# Droid_meter_rev2.net
KiCad netlist of a schematic drawn in EAGLE
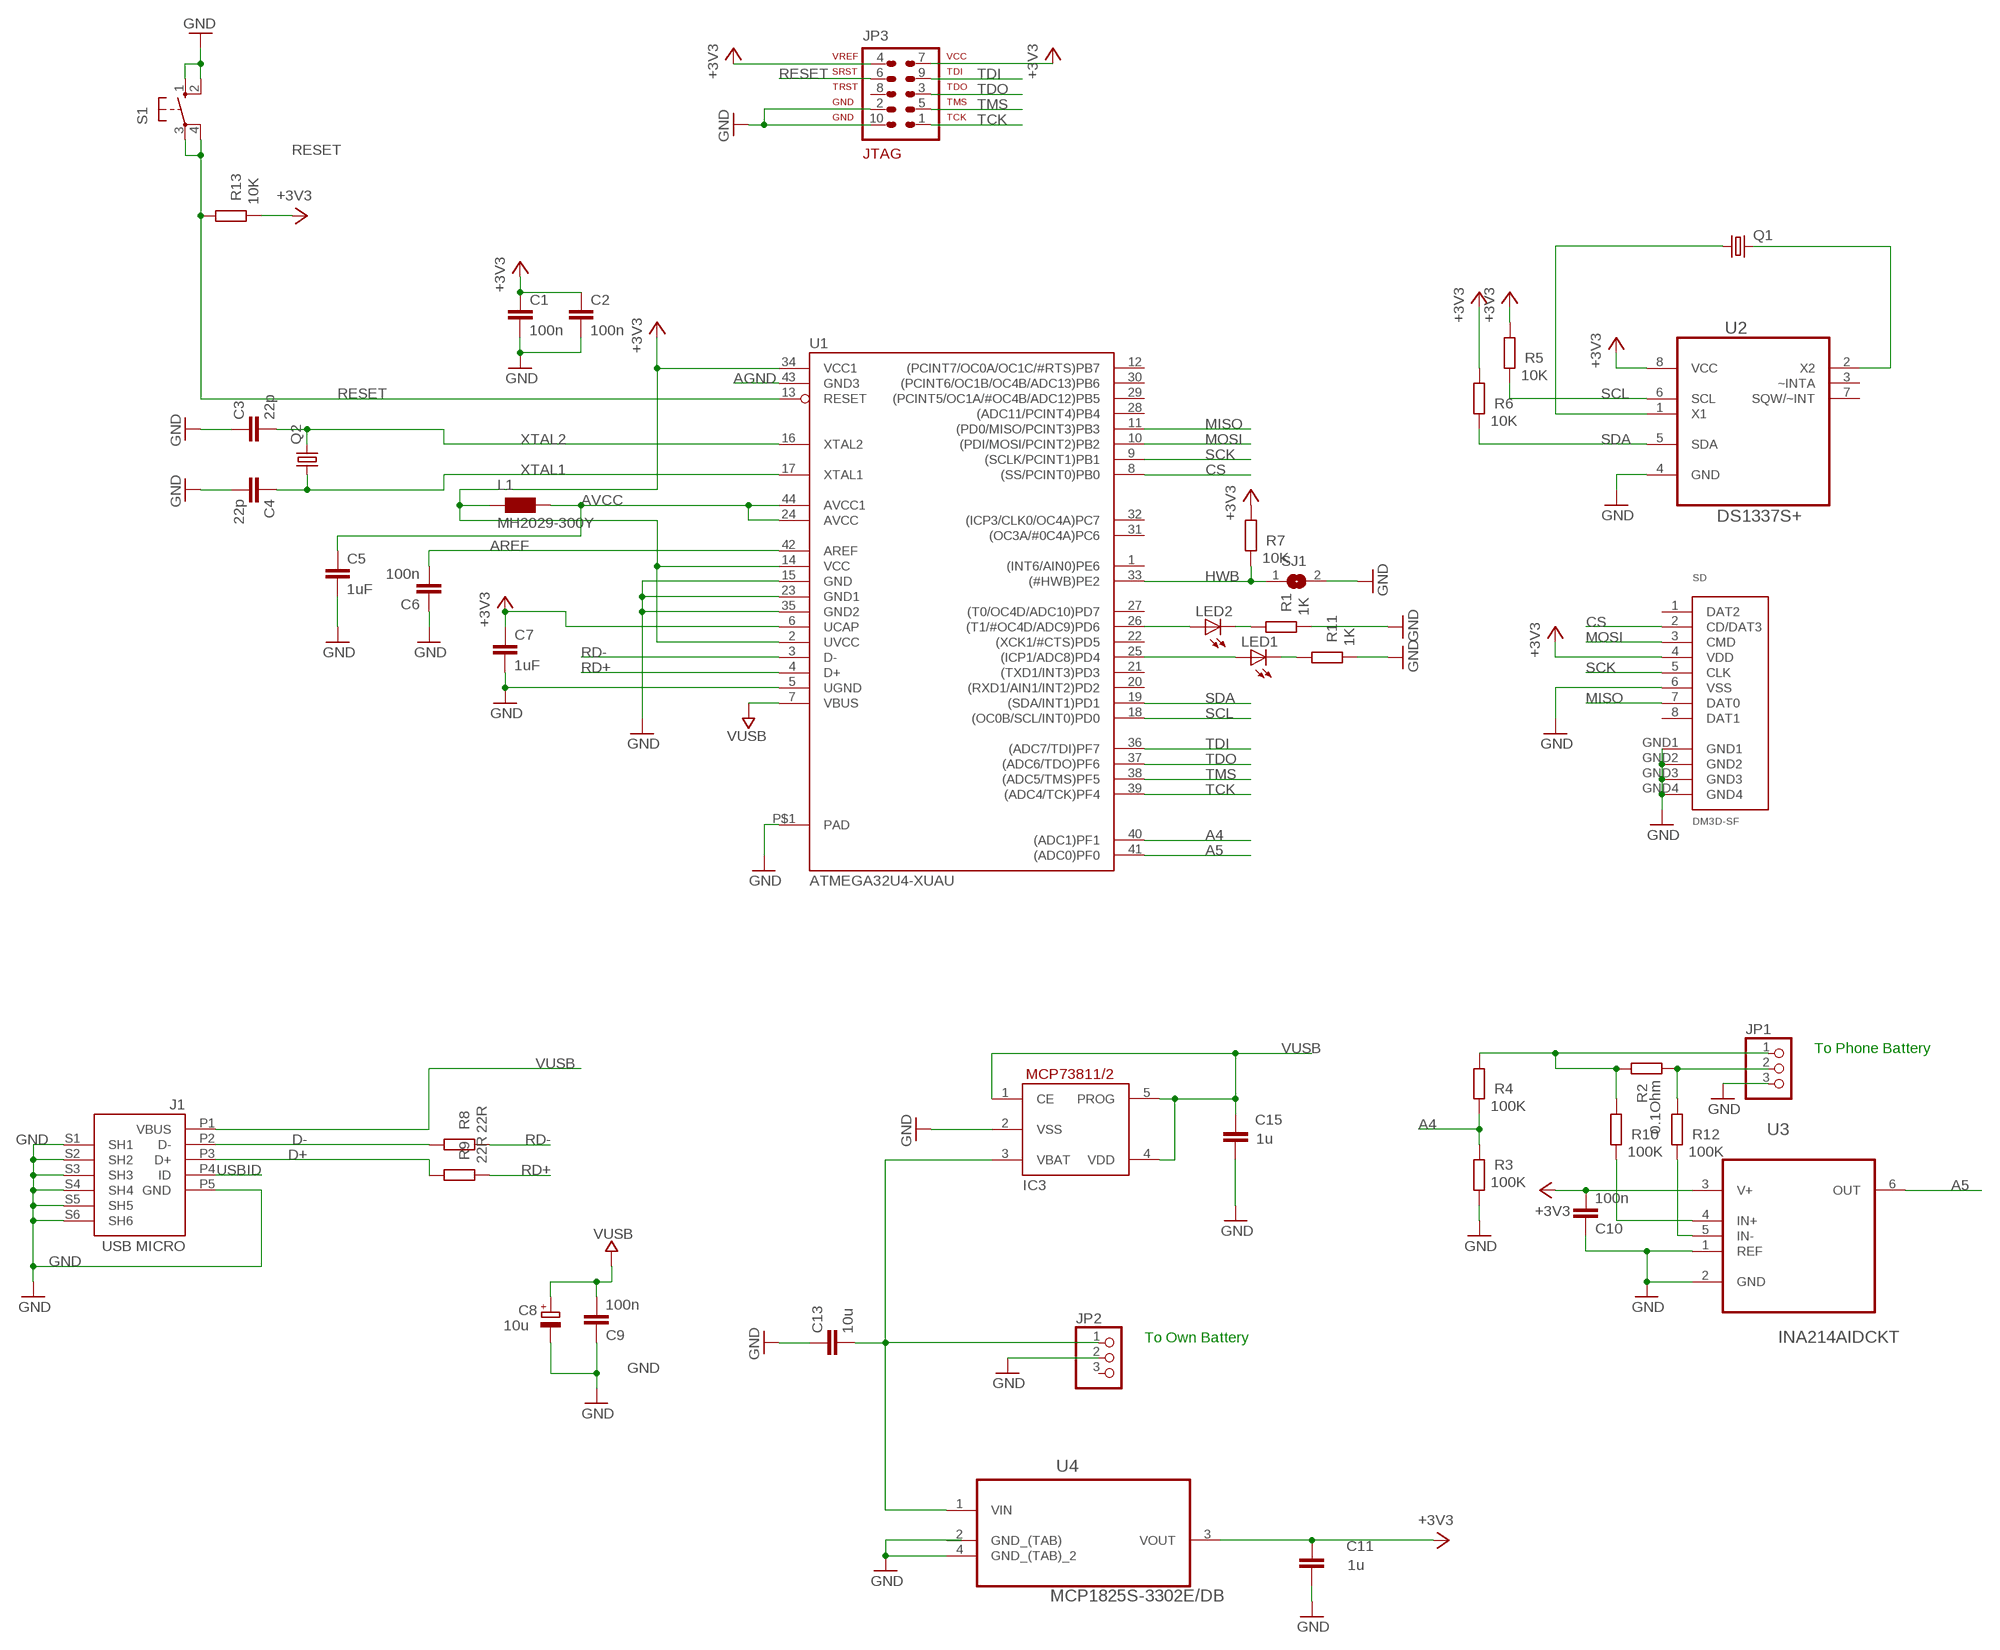
[diagram p0: schematic, sheet 1]

(export (version "E")
  (design (tool "Eeschema 10.0.6"))
  (components
    (comp (ref "C1")
      (value "100n")
      (footprint "eagle-import:C0603-ROUND")
      (libsource (lib "eagle-import") (part "C-EUC0603"))
    )
    (comp (ref "C2")
      (value "100n")
      (footprint "eagle-import:C0603-ROUND")
      (libsource (lib "eagle-import") (part "C-EUC0603"))
    )
    (comp (ref "C3")
      (value "22p")
      (footprint "eagle-import:C0603-ROUND")
      (libsource (lib "eagle-import") (part "C-EUC0603"))
    )
    (comp (ref "C4")
      (value "22p")
      (footprint "eagle-import:C0603-ROUND")
      (libsource (lib "eagle-import") (part "C-EUC0603"))
    )
    (comp (ref "C5")
      (value "1uF")
      (footprint "eagle-import:C0603-ROUND")
      (libsource (lib "eagle-import") (part "C-EUC0603"))
    )
    (comp (ref "C6")
      (value "100n")
      (footprint "eagle-import:C0603-ROUND")
      (libsource (lib "eagle-import") (part "C-EUC0603"))
    )
    (comp (ref "C7")
      (value "1uF")
      (footprint "eagle-import:C0603-ROUND")
      (libsource (lib "eagle-import") (part "C-EUC0603"))
    )
    (comp (ref "C8")
      (value "10u")
      (footprint "eagle-import:SMC_B")
      (libsource (lib "eagle-import") (part "CPOL-EUSMCB"))
    )
    (comp (ref "C9")
      (value "100n")
      (footprint "eagle-import:C0603-ROUND")
      (libsource (lib "eagle-import") (part "C-EUC0603"))
    )
    (comp (ref "C10")
      (value "100n")
      (footprint "eagle-import:C0603-ROUND")
      (libsource (lib "eagle-import") (part "C-EUC0603"))
    )
    (comp (ref "C11")
      (value "1u")
      (footprint "eagle-import:C0603-ROUND")
      (libsource (lib "eagle-import") (part "C-EUC0603"))
    )
    (comp (ref "C13")
      (value "10u")
      (footprint "eagle-import:C0805")
      (libsource (lib "eagle-import") (part "rcl_C-EUC0805"))
    )
    (comp (ref "C15")
      (value "1u")
      (footprint "eagle-import:C0603-ROUND")
      (libsource (lib "eagle-import") (part "C-EUC0603"))
    )
    (comp (ref "IC3")
      (value "MCP73811/2")
      (footprint "eagle-import:SOT23-5L")
      (libsource (lib "eagle-import") (part "MCP73811/2"))
    )
    (comp (ref "J1")
      (value "USB MICRO")
      (footprint "eagle-import:CON2_USB_MICRO_B_AT")
      (libsource (lib "eagle-import") (part "MYCON2_USB-MINI-B"))
    )
    (comp (ref "JP1")
      (value "PINHD-1X3")
      (footprint "eagle-import:1X03")
      (libsource (lib "eagle-import") (part "PINHD-1X3"))
    )
    (comp (ref "JP2")
      (value "PINHD-1X3")
      (footprint "eagle-import:1X03")
      (libsource (lib "eagle-import") (part "PINHD-1X3"))
    )
    (comp (ref "JP3")
      (value "AVR-JTAG-10")
      (footprint "eagle-import:AVR-JTAG-10")
      (libsource (lib "eagle-import") (part "AVR-JTAG-10"))
    )
    (comp (ref "L1")
      (value "MH2029-300Y")
      (footprint "eagle-import:0805")
      (libsource (lib "eagle-import") (part "WE-CBF_0805"))
    )
    (comp (ref "LED1")
      (value "LEDCHIP-LED0603")
      (footprint "eagle-import:CHIP-LED0603")
      (libsource (lib "eagle-import") (part "LEDCHIP-LED0603"))
    )
    (comp (ref "LED2")
      (value "LEDCHIP-LED0603")
      (footprint "eagle-import:CHIP-LED0603")
      (libsource (lib "eagle-import") (part "LEDCHIP-LED0603"))
    )
    (comp (ref "Q1")
      (value "CRYSTALMM39SL")
      (footprint "eagle-import:MM39SL")
      (libsource (lib "eagle-import") (part "CRYSTALMM39SL"))
    )
    (comp (ref "Q2")
      (value "CRYSTALCTS406")
      (footprint "eagle-import:CTS406")
      (libsource (lib "eagle-import") (part "CRYSTALCTS406"))
    )
    (comp (ref "R1")
      (value "1K")
      (footprint "eagle-import:R0603-ROUND")
      (libsource (lib "eagle-import") (part "R-EU_R0603"))
    )
    (comp (ref "R2")
      (value "0.1Ohm")
      (footprint "eagle-import:R2512")
      (libsource (lib "eagle-import") (part "R-EU_R2512"))
    )
    (comp (ref "R3")
      (value "100K")
      (footprint "eagle-import:R0603-ROUND")
      (libsource (lib "eagle-import") (part "R-EU_R0603"))
    )
    (comp (ref "R4")
      (value "100K")
      (footprint "eagle-import:R0603-ROUND")
      (libsource (lib "eagle-import") (part "R-EU_R0603"))
    )
    (comp (ref "R5")
      (value "10K")
      (footprint "eagle-import:R0603-ROUND")
      (libsource (lib "eagle-import") (part "R-EU_R0603"))
    )
    (comp (ref "R6")
      (value "10K")
      (footprint "eagle-import:R0603-ROUND")
      (libsource (lib "eagle-import") (part "R-EU_R0603"))
    )
    (comp (ref "R7")
      (value "10K")
      (footprint "eagle-import:R0603-ROUND")
      (libsource (lib "eagle-import") (part "R-EU_R0603"))
    )
    (comp (ref "R8")
      (value "22R")
      (footprint "eagle-import:R0603-ROUND")
      (libsource (lib "eagle-import") (part "R-EU_R0603"))
    )
    (comp (ref "R9")
      (value "22R")
      (footprint "eagle-import:R0603-ROUND")
      (libsource (lib "eagle-import") (part "R-EU_R0603"))
    )
    (comp (ref "R10")
      (value "100K")
      (footprint "eagle-import:R0603-ROUND")
      (libsource (lib "eagle-import") (part "R-EU_R0603"))
    )
    (comp (ref "R11")
      (value "1K")
      (footprint "eagle-import:R0603-ROUND")
      (libsource (lib "eagle-import") (part "R-EU_R0603"))
    )
    (comp (ref "R12")
      (value "100K")
      (footprint "eagle-import:R0603-ROUND")
      (libsource (lib "eagle-import") (part "R-EU_R0603"))
    )
    (comp (ref "R13")
      (value "10K")
      (footprint "eagle-import:R0603-ROUND")
      (libsource (lib "eagle-import") (part "R-EU_R0603"))
    )
    (comp (ref "S1")
      (value "10-XX")
      (footprint "eagle-import:B3F-10XX")
      (libsource (lib "eagle-import") (part "10-XX"))
    )
    (comp (ref "SD")
      (value "DM3D-SF")
      (footprint "eagle-import:DM3D-SF")
      (libsource (lib "eagle-import") (part "DM3D-SF"))
    )
    (comp (ref "SJ1") (value "SJ") (footprint "eagle-import:SJ") (libsource (lib "eagle-import") (part "SJ")))
    (comp (ref "U1")
      (value "ATMEGA32U4-XUAU")
      (footprint "eagle-import:TQFP44-PAD")
      (libsource (lib "eagle-import") (part "ATMEGA32U4-XUAU"))
    )
    (comp (ref "U2")
      (value "DS1337S+")
      (footprint "eagle-import:SOIC127P600X175-8N")
      (libsource (lib "eagle-import") (part "DS1337S+"))
    )
    (comp (ref "U3")
      (value "INA214AIDCKT")
      (footprint "eagle-import:SOT65P210X110-6N")
      (libsource (lib "eagle-import") (part "INA214AIDCKT"))
    )
    (comp (ref "U4")
      (value "MCP1825S-3302E/DB")
      (footprint "eagle-import:SOT230P700X180-4N")
      (libsource (lib "eagle-import") (part "MCP1825S-3302E/DB"))
    )
  )
  (nets
    (net (code "1") (name "+3V3") (class "Default")
      (node (ref "C1") (pin "1") (pinfunction "1_1") (pintype "passive"))
      (node (ref "C10") (pin "2") (pinfunction "2_2") (pintype "passive"))
      (node (ref "C11") (pin "2") (pinfunction "2_2") (pintype "passive"))
      (node (ref "C2") (pin "1") (pinfunction "1_1") (pintype "passive"))
      (node (ref "C7") (pin "1") (pinfunction "1_1") (pintype "passive"))
      (node (ref "JP3") (pin "4") (pinfunction "4_4") (pintype "passive"))
      (node (ref "JP3") (pin "7") (pinfunction "7_7") (pintype "passive"))
      (node (ref "L1") (pin "1") (pinfunction "1_1") (pintype "passive"))
      (node (ref "R13") (pin "2") (pinfunction "2_2") (pintype "passive"))
      (node (ref "R5") (pin "1") (pinfunction "1_1") (pintype "passive"))
      (node (ref "R6") (pin "1") (pinfunction "1_1") (pintype "passive"))
      (node (ref "R7") (pin "1") (pinfunction "1_1") (pintype "passive"))
      (node (ref "SD") (pin "4") (pinfunction "VDD_4") (pintype "bidirectional"))
      (node (ref "U1") (pin "14") (pinfunction "VCC_14") (pintype "power_in"))
      (node (ref "U1") (pin "2") (pinfunction "UVCC_2") (pintype "power_in"))
      (node (ref "U1") (pin "34") (pinfunction "VCC1_34") (pintype "power_in"))
      (node (ref "U1") (pin "6") (pinfunction "UCAP_6") (pintype "passive"))
      (node (ref "U2") (pin "8") (pinfunction "VCC_8") (pintype "power_in"))
      (node (ref "U3") (pin "3") (pinfunction "V+_3") (pintype "power_in"))
      (node (ref "U4") (pin "3") (pinfunction "VOUT_3") (pintype "output"))
    )
    (net (code "2") (name "/A4") (class "Default")
      (node (ref "R3") (pin "1") (pinfunction "1_1") (pintype "passive"))
      (node (ref "R4") (pin "2") (pinfunction "2_2") (pintype "passive"))
      (node (ref "U1") (pin "40") (pinfunction "(ADC1)PF1_40") (pintype "bidirectional"))
    )
    (net (code "3") (name "/A5") (class "Default")
      (node (ref "U1") (pin "41") (pinfunction "(ADC0)PF0_41") (pintype "bidirectional"))
      (node (ref "U3") (pin "6") (pinfunction "OUT_6") (pintype "output"))
    )
    (net (code "4") (name "/AGND") (class "Default")
      (node (ref "U1") (pin "43") (pinfunction "GND3_43") (pintype "power_in"))
    )
    (net (code "5") (name "/AREF") (class "Default")
      (node (ref "C6") (pin "2") (pinfunction "2_2") (pintype "passive"))
      (node (ref "U1") (pin "42") (pinfunction "AREF_42") (pintype "power_in"))
    )
    (net (code "6") (name "/AVCC") (class "Default")
      (node (ref "C5") (pin "1") (pinfunction "1_1") (pintype "passive"))
      (node (ref "L1") (pin "2") (pinfunction "2_2") (pintype "passive"))
      (node (ref "U1") (pin "24") (pinfunction "AVCC_24") (pintype "power_in"))
      (node (ref "U1") (pin "44") (pinfunction "AVCC1_44") (pintype "power_in"))
    )
    (net (code "7") (name "/CS") (class "Default")
      (node (ref "SD") (pin "2") (pinfunction "CD/DAT3_2") (pintype "bidirectional"))
      (node (ref "U1") (pin "8") (pinfunction "(SS/PCINT0)PB0_8") (pintype "bidirectional"))
    )
    (net (code "8") (name "/D+") (class "Default")
      (node (ref "J1") (pin "P3") (pinfunction "D+_P3") (pintype "bidirectional"))
      (node (ref "R9") (pin "1") (pinfunction "1_1") (pintype "passive"))
    )
    (net (code "9") (name "/D-") (class "Default")
      (node (ref "J1") (pin "P2") (pinfunction "D-_P2") (pintype "bidirectional"))
      (node (ref "R8") (pin "1") (pinfunction "1_1") (pintype "passive"))
    )
    (net (code "10") (name "/HWB") (class "Default")
      (node (ref "R7") (pin "2") (pinfunction "2_2") (pintype "passive"))
      (node (ref "SJ1") (pin "1") (pinfunction "1_1") (pintype "passive"))
      (node (ref "U1") (pin "33") (pinfunction "(#HWB)PE2_33") (pintype "bidirectional"))
    )
    (net (code "11") (name "/MISO") (class "Default")
      (node (ref "SD") (pin "7") (pinfunction "DAT0_7") (pintype "bidirectional"))
      (node (ref "U1") (pin "11") (pinfunction "(PD0/MISO/PCINT3)PB3_11") (pintype "bidirectional"))
    )
    (net (code "12") (name "/MOSI") (class "Default")
      (node (ref "SD") (pin "3") (pinfunction "CMD_3") (pintype "bidirectional"))
      (node (ref "U1") (pin "10") (pinfunction "(PDI/MOSI/PCINT2)PB2_10") (pintype "bidirectional"))
    )
    (net (code "13") (name "/RD+") (class "Default")
      (node (ref "R9") (pin "2") (pinfunction "2_2") (pintype "passive"))
      (node (ref "U1") (pin "4") (pinfunction "D+_4") (pintype "bidirectional"))
    )
    (net (code "14") (name "/RD-") (class "Default")
      (node (ref "R8") (pin "2") (pinfunction "2_2") (pintype "passive"))
      (node (ref "U1") (pin "3") (pinfunction "D-_3") (pintype "bidirectional"))
    )
    (net (code "15") (name "/RESET") (class "Default")
      (node (ref "JP3") (pin "6") (pinfunction "6_6") (pintype "passive"))
      (node (ref "R13") (pin "1") (pinfunction "1_1") (pintype "passive"))
      (node (ref "S1") (pin "3") (pinfunction "P_3") (pintype "passive"))
      (node (ref "S1") (pin "4") (pinfunction "P1_4") (pintype "passive"))
      (node (ref "U1") (pin "13") (pinfunction "RESET_13") (pintype "input"))
    )
    (net (code "16") (name "/SCK") (class "Default")
      (node (ref "SD") (pin "5") (pinfunction "CLK_5") (pintype "bidirectional"))
      (node (ref "U1") (pin "9") (pinfunction "(SCLK/PCINT1)PB1_9") (pintype "bidirectional"))
    )
    (net (code "17") (name "/SCL") (class "Default")
      (node (ref "R5") (pin "2") (pinfunction "2_2") (pintype "passive"))
      (node (ref "U1") (pin "18") (pinfunction "(OC0B/SCL/INT0)PD0_18") (pintype "bidirectional"))
      (node (ref "U2") (pin "6") (pinfunction "SCL_6") (pintype "input"))
    )
    (net (code "18") (name "/SDA") (class "Default")
      (node (ref "R6") (pin "2") (pinfunction "2_2") (pintype "passive"))
      (node (ref "U1") (pin "19") (pinfunction "(SDA/INT1)PD1_19") (pintype "bidirectional"))
      (node (ref "U2") (pin "5") (pinfunction "SDA_5") (pintype "bidirectional"))
    )
    (net (code "19") (name "/TCK") (class "Default")
      (node (ref "JP3") (pin "1") (pinfunction "1_1") (pintype "passive"))
      (node (ref "U1") (pin "39") (pinfunction "(ADC4/TCK)PF4_39") (pintype "bidirectional"))
    )
    (net (code "20") (name "/TDI") (class "Default")
      (node (ref "JP3") (pin "9") (pinfunction "9_9") (pintype "passive"))
      (node (ref "U1") (pin "36") (pinfunction "(ADC7/TDI)PF7_36") (pintype "bidirectional"))
    )
    (net (code "21") (name "/TDO") (class "Default")
      (node (ref "JP3") (pin "3") (pinfunction "3_3") (pintype "passive"))
      (node (ref "U1") (pin "37") (pinfunction "(ADC6/TDO)PF6_37") (pintype "bidirectional"))
    )
    (net (code "22") (name "/TMS") (class "Default")
      (node (ref "JP3") (pin "5") (pinfunction "5_5") (pintype "passive"))
      (node (ref "U1") (pin "38") (pinfunction "(ADC5/TMS)PF5_38") (pintype "bidirectional"))
    )
    (net (code "23") (name "/USBID") (class "Default")
      (node (ref "J1") (pin "P4") (pinfunction "ID_P4") (pintype "bidirectional"))
    )
    (net (code "24") (name "/XTAL1") (class "Default")
      (node (ref "C4") (pin "1") (pinfunction "1_1") (pintype "passive"))
      (node (ref "Q2") (pin "1") (pinfunction "1_1") (pintype "passive"))
      (node (ref "U1") (pin "17") (pinfunction "XTAL1_17") (pintype "bidirectional"))
    )
    (net (code "25") (name "/XTAL2") (class "Default")
      (node (ref "C3") (pin "2") (pinfunction "2_2") (pintype "passive"))
      (node (ref "Q2") (pin "3") (pinfunction "2_3") (pintype "passive"))
      (node (ref "U1") (pin "16") (pinfunction "XTAL2_16") (pintype "bidirectional"))
    )
    (net (code "26") (name "GND") (class "Default")
      (node (ref "C1") (pin "2") (pinfunction "2_2") (pintype "passive"))
      (node (ref "C10") (pin "1") (pinfunction "1_1") (pintype "passive"))
      (node (ref "C11") (pin "1") (pinfunction "1_1") (pintype "passive"))
      (node (ref "C13") (pin "1") (pinfunction "1_1") (pintype "passive"))
      (node (ref "C15") (pin "1") (pinfunction "1_1") (pintype "passive"))
      (node (ref "C2") (pin "2") (pinfunction "2_2") (pintype "passive"))
      (node (ref "C3") (pin "1") (pinfunction "1_1") (pintype "passive"))
      (node (ref "C4") (pin "2") (pinfunction "2_2") (pintype "passive"))
      (node (ref "C5") (pin "2") (pinfunction "2_2") (pintype "passive"))
      (node (ref "C6") (pin "1") (pinfunction "1_1") (pintype "passive"))
      (node (ref "C7") (pin "2") (pinfunction "2_2") (pintype "passive"))
      (node (ref "C8") (pin "-") (pinfunction "-_-") (pintype "passive"))
      (node (ref "C9") (pin "1") (pinfunction "1_1") (pintype "passive"))
      (node (ref "IC3") (pin "2") (pinfunction "VSS_2") (pintype "power_in"))
      (node (ref "J1") (pin "P5") (pinfunction "GND_P5") (pintype "passive"))
      (node (ref "J1") (pin "S1") (pinfunction "SH1_S1") (pintype "passive"))
      (node (ref "J1") (pin "S2") (pinfunction "SH2_S2") (pintype "passive"))
      (node (ref "J1") (pin "S3") (pinfunction "SH3_S3") (pintype "passive"))
      (node (ref "J1") (pin "S4") (pinfunction "SH4_S4") (pintype "passive"))
      (node (ref "J1") (pin "S5") (pinfunction "SH5_S5") (pintype "passive"))
      (node (ref "J1") (pin "S6") (pinfunction "SH6_S6") (pintype "passive"))
      (node (ref "JP1") (pin "3") (pinfunction "3_3") (pintype "passive"))
      (node (ref "JP2") (pin "2") (pinfunction "2_2") (pintype "passive"))
      (node (ref "JP3") (pin "10") (pinfunction "10_10") (pintype "passive"))
      (node (ref "JP3") (pin "2") (pinfunction "2_2") (pintype "passive"))
      (node (ref "R1") (pin "2") (pinfunction "2_2") (pintype "passive"))
      (node (ref "R11") (pin "2") (pinfunction "2_2") (pintype "passive"))
      (node (ref "R3") (pin "2") (pinfunction "2_2") (pintype "passive"))
      (node (ref "S1") (pin "1") (pinfunction "S_1") (pintype "passive"))
      (node (ref "S1") (pin "2") (pinfunction "S1_2") (pintype "passive"))
      (node (ref "SD") (pin "6") (pinfunction "VSS_6") (pintype "bidirectional"))
      (node (ref "SD") (pin "GND1") (pinfunction "GND1_GND1") (pintype "bidirectional"))
      (node (ref "SD") (pin "GND2") (pinfunction "GND2_GND2") (pintype "bidirectional"))
      (node (ref "SD") (pin "GND3") (pinfunction "GND3_GND3") (pintype "bidirectional"))
      (node (ref "SD") (pin "GND4") (pinfunction "GND4_GND4") (pintype "bidirectional"))
      (node (ref "SJ1") (pin "2") (pinfunction "2_2") (pintype "passive"))
      (node (ref "U1") (pin "15") (pinfunction "GND_15") (pintype "power_in"))
      (node (ref "U1") (pin "23") (pinfunction "GND1_23") (pintype "power_in"))
      (node (ref "U1") (pin "35") (pinfunction "GND2_35") (pintype "power_in"))
      (node (ref "U1") (pin "5") (pinfunction "UGND_5") (pintype "power_in"))
      (node (ref "U1") (pin "P$1") (pinfunction "PAD_P$1") (pintype "power_in"))
      (node (ref "U2") (pin "4") (pinfunction "GND_4") (pintype "passive"))
      (node (ref "U3") (pin "1") (pinfunction "REF_1") (pintype "input"))
      (node (ref "U3") (pin "2") (pinfunction "GND_2") (pintype "passive"))
      (node (ref "U4") (pin "4") (pinfunction "GND_(TAB)_2_4") (pintype "passive"))
    )
    (net (code "27") (name "Net-(IC3-VBAT)") (class "Default")
      (node (ref "C13") (pin "2") (pinfunction "2_2") (pintype "passive"))
      (node (ref "IC3") (pin "3") (pinfunction "VBAT_3") (pintype "bidirectional"))
      (node (ref "JP2") (pin "1") (pinfunction "1_1") (pintype "passive"))
      (node (ref "U4") (pin "1") (pinfunction "VIN_1") (pintype "input"))
    )
    (net (code "28") (name "Net-(JP1-Pad1)") (class "Default")
      (node (ref "JP1") (pin "1") (pinfunction "1_1") (pintype "passive"))
      (node (ref "R10") (pin "1") (pinfunction "1_1") (pintype "passive"))
      (node (ref "R2") (pin "2") (pinfunction "2_2") (pintype "passive"))
      (node (ref "R4") (pin "1") (pinfunction "1_1") (pintype "passive"))
    )
    (net (code "29") (name "Net-(JP1-Pad2)") (class "Default")
      (node (ref "JP1") (pin "2") (pinfunction "2_2") (pintype "passive"))
      (node (ref "R12") (pin "1") (pinfunction "1_1") (pintype "passive"))
      (node (ref "R2") (pin "1") (pinfunction "1_1") (pintype "passive"))
    )
    (net (code "30") (name "Net-(LED1-PadC)") (class "Default")
      (node (ref "LED1") (pin "C") (pinfunction "C_C") (pintype "passive"))
      (node (ref "R11") (pin "1") (pinfunction "1_1") (pintype "passive"))
    )
    (net (code "31") (name "Net-(LED2-PadC)") (class "Default")
      (node (ref "LED2") (pin "C") (pinfunction "C_C") (pintype "passive"))
      (node (ref "R1") (pin "1") (pinfunction "1_1") (pintype "passive"))
    )
    (net (code "32") (name "Net-(Q1-2)") (class "Default")
      (node (ref "Q1") (pin "4") (pinfunction "2_4") (pintype "passive"))
      (node (ref "U2") (pin "2") (pinfunction "X2_2") (pintype "passive"))
    )
    (net (code "33") (name "Net-(U1-(ICP1{slash}ADC8)PD4)") (class "Default")
      (node (ref "LED1") (pin "A") (pinfunction "A_A") (pintype "passive"))
      (node (ref "U1") (pin "25") (pinfunction "(ICP1/ADC8)PD4_25") (pintype "bidirectional"))
    )
    (net (code "34") (name "Net-(U1-(T1{slash}#OC4D{slash}ADC9)PD6)") (class "Default")
      (node (ref "LED2") (pin "A") (pinfunction "A_A") (pintype "passive"))
      (node (ref "U1") (pin "26") (pinfunction "(T1/#OC4D/ADC9)PD6_26") (pintype "bidirectional"))
    )
    (net (code "35") (name "Net-(U2-X1)") (class "Default")
      (node (ref "Q1") (pin "1") (pinfunction "1_1") (pintype "passive"))
      (node (ref "U2") (pin "1") (pinfunction "X1_1") (pintype "input"))
    )
    (net (code "36") (name "Net-(U3-IN+)") (class "Default")
      (node (ref "R10") (pin "2") (pinfunction "2_2") (pintype "passive"))
      (node (ref "U3") (pin "4") (pinfunction "IN+_4") (pintype "input"))
    )
    (net (code "37") (name "Net-(U3-IN-)") (class "Default")
      (node (ref "R12") (pin "2") (pinfunction "2_2") (pintype "passive"))
      (node (ref "U3") (pin "5") (pinfunction "IN-_5") (pintype "input"))
    )
    (net (code "38") (name "VUSB") (class "Default")
      (node (ref "C15") (pin "2") (pinfunction "2_2") (pintype "passive"))
      (node (ref "C8") (pin "+") (pinfunction "+_+") (pintype "passive"))
      (node (ref "C9") (pin "2") (pinfunction "2_2") (pintype "passive"))
      (node (ref "IC3") (pin "1") (pinfunction "CE_1") (pintype "input"))
      (node (ref "IC3") (pin "4") (pinfunction "VDD_4") (pintype "power_in"))
      (node (ref "IC3") (pin "5") (pinfunction "PROG_5") (pintype "input"))
      (node (ref "J1") (pin "P1") (pinfunction "VBUS_P1") (pintype "power_in"))
      (node (ref "U1") (pin "7") (pinfunction "VBUS_7") (pintype "input"))
    )
    (net (code "39") (name "unconnected-(JP2-Pad3)") (class "Default")
      (node (ref "JP2") (pin "3") (pinfunction "3_3") (pintype "passive"))
    )
    (net (code "40") (name "unconnected-(JP3-Pad8)") (class "Default")
      (node (ref "JP3") (pin "8") (pinfunction "8_8") (pintype "passive"))
    )
    (net (code "41") (name "unconnected-(SD-DAT1-Pad8)") (class "Default")
      (node (ref "SD") (pin "8") (pinfunction "DAT1_8") (pintype "bidirectional"))
    )
    (net (code "42") (name "unconnected-(SD-DAT2-Pad1)") (class "Default")
      (node (ref "SD") (pin "1") (pinfunction "DAT2_1") (pintype "bidirectional"))
    )
    (net (code "43") (name "unconnected-(U1-(ADC11{slash}PCINT4)PB4-Pad28)") (class "Default")
      (node (ref "U1") (pin "28") (pinfunction "(ADC11/PCINT4)PB4_28") (pintype "bidirectional"))
    )
    (net (code "44") (name "unconnected-(U1-(ICP3{slash}CLK0{slash}OC4A)PC7-Pad32)") (class "Default")
      (node (ref "U1") (pin "32") (pinfunction "(ICP3/CLK0/OC4A)PC7_32") (pintype "bidirectional"))
    )
    (net (code "45") (name "unconnected-(U1-(INT6{slash}AIN0)PE6-Pad1)") (class "Default")
      (node (ref "U1") (pin "1") (pinfunction "(INT6/AIN0)PE6_1") (pintype "bidirectional"))
    )
    (net (code "46") (name "unconnected-(U1-(OC3A{slash}#0C4A)PC6-Pad31)") (class "Default")
      (node (ref "U1") (pin "31") (pinfunction "(OC3A/#0C4A)PC6_31") (pintype "bidirectional"))
    )
    (net (code "47") (name "unconnected-(U1-(PCINT5{slash}OC1A{slash}#OC4B{slash}ADC12)PB5-Pad29)") (class "Default")
      (node (ref "U1") (pin "29") (pinfunction "(PCINT5/OC1A/#OC4B/ADC12)PB5_29") (pintype "bidirectional"))
    )
    (net (code "48") (name "unconnected-(U1-(PCINT6{slash}OC1B{slash}OC4B{slash}ADC13)PB6-Pad30)") (class "Default")
      (node (ref "U1") (pin "30") (pinfunction "(PCINT6/OC1B/OC4B/ADC13)PB6_30") (pintype "bidirectional"))
    )
    (net (code "49") (name "unconnected-(U1-(PCINT7{slash}OC0A{slash}OC1C{slash}#RTS)PB7-Pad12)") (class "Default")
      (node (ref "U1") (pin "12") (pinfunction "(PCINT7/OC0A/OC1C/#RTS)PB7_12") (pintype "bidirectional"))
    )
    (net (code "50") (name "unconnected-(U1-(RXD1{slash}AIN1{slash}INT2)PD2-Pad20)") (class "Default")
      (node (ref "U1") (pin "20") (pinfunction "(RXD1/AIN1/INT2)PD2_20") (pintype "bidirectional"))
    )
    (net (code "51") (name "unconnected-(U1-(T0{slash}OC4D{slash}ADC10)PD7-Pad27)") (class "Default")
      (node (ref "U1") (pin "27") (pinfunction "(T0/OC4D/ADC10)PD7_27") (pintype "bidirectional"))
    )
    (net (code "52") (name "unconnected-(U1-(TXD1{slash}INT3)PD3-Pad21)") (class "Default")
      (node (ref "U1") (pin "21") (pinfunction "(TXD1/INT3)PD3_21") (pintype "bidirectional"))
    )
    (net (code "53") (name "unconnected-(U1-(XCK1{slash}#CTS)PD5-Pad22)") (class "Default")
      (node (ref "U1") (pin "22") (pinfunction "(XCK1/#CTS)PD5_22") (pintype "bidirectional"))
    )
    (net (code "54") (name "unconnected-(U2-SQW{slash}~{INT}-Pad7)") (class "Default")
      (node (ref "U2") (pin "7") (pinfunction "SQW/~{INT}_7") (pintype "output"))
    )
    (net (code "55") (name "unconnected-(U2-~{INTA}-Pad3)") (class "Default")
      (node (ref "U2") (pin "3") (pinfunction "~{INTA}_3") (pintype "output"))
    )
    (net (code "56") (name "unconnected-(U4-GND_(TAB)-Pad2)") (class "Default")
      (node (ref "U4") (pin "2") (pinfunction "GND_(TAB)_2") (pintype "passive"))
    )
  )
)
